# MCU.net
KiCad netlist of a schematic drawn in Altium Designer
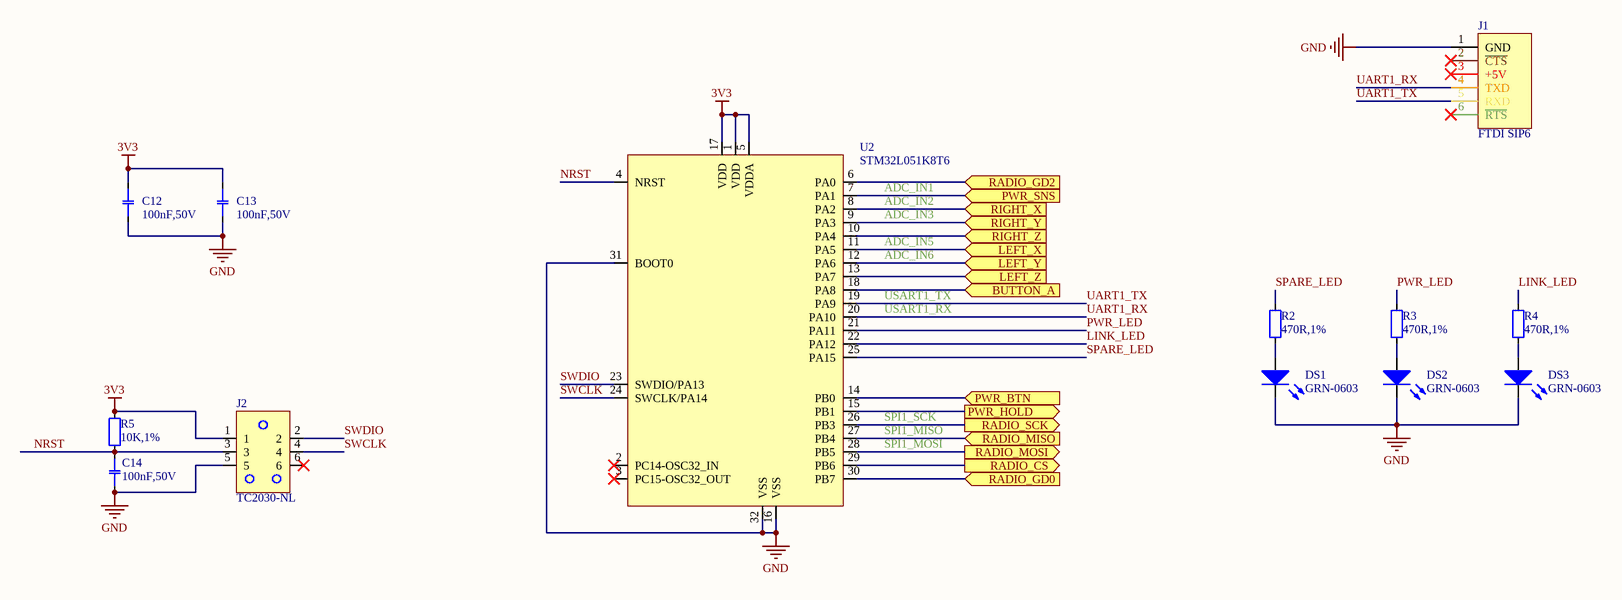
[diagram p0: MCU.SchDoc]

(export (version "E")
  (design (tool "Eeschema 10.0.6"))
  (components
    (comp (ref "C12")
      (value "100nF,50V")
      (footprint "CAPC1608X09N_0603")
      (description "CAP CER 0.1UF 50V 10% X7R 0603")
      (fields (field (name "MANUFACTURER") "Kemet") (field (name "TOLERANCE") "10%"))
      (libsource (lib "library") (part "CAP-NP_1"))
    )
    (comp (ref "C13")
      (value "100nF,50V")
      (footprint "CAPC1608X09N_0603")
      (description "CAP CER 0.1UF 50V 10% X7R 0603")
      (fields (field (name "MANUFACTURER") "Kemet") (field (name "TOLERANCE") "10%"))
      (libsource (lib "library") (part "CAP-NP_1"))
    )
    (comp (ref "C14")
      (value "100nF,50V")
      (footprint "CAPC1608X09N_0603")
      (description "CAP CER 0.1UF 50V 10% X7R 0603")
      (fields (field (name "MANUFACTURER") "Kemet") (field (name "TOLERANCE") "10%"))
      (libsource (lib "library") (part "CAP-NP_1"))
    )
    (comp (ref "DS1")
      (value "GRN-0603")
      (footprint "LED_SML-LX0603")
      (description "LED GREEN CLEAR 0603 SMD")
      (fields
        (field (name "MANUFACTURER") "Dialight")
        (field (name "MANUFACTURER PART NUMBER") "5988081107F")
      )
      (libsource (lib "library") (part "LED_1"))
    )
    (comp (ref "DS2")
      (value "GRN-0603")
      (footprint "LED_SML-LX0603")
      (description "LED GREEN CLEAR 0603 SMD")
      (fields
        (field (name "MANUFACTURER") "Dialight")
        (field (name "MANUFACTURER PART NUMBER") "5988081107F")
      )
      (libsource (lib "library") (part "LED_1"))
    )
    (comp (ref "DS3")
      (value "GRN-0603")
      (footprint "LED_SML-LX0603")
      (description "LED GREEN CLEAR 0603 SMD")
      (fields
        (field (name "MANUFACTURER") "Dialight")
        (field (name "MANUFACTURER PART NUMBER") "5988081107F")
      )
      (libsource (lib "library") (part "LED_1"))
    )
    (comp (ref "J1")
      (value "FTDI SIP6")
      (footprint "HIROSE_A2-6PA-2.54DSA")
      (description "FTDI Serial Header")
      (fields
        (field (name "MANUFACTURER") "Hirose Electric Co Ltd")
        (field (name "MANUFACTURER PART NUMBER") "A2-6PA-2.54DSA(71)")
      )
      (libsource (lib "library") (part "FTDI_TTL_232R"))
    )
    (comp (ref "J2")
      (value "TC2030-NL")
      (footprint "TAGCON_TC2030-IDC-NL")
      (description "Tag connect 6 way - No Legs")
      (libsource (lib "library") (part "TAGCON_TC2030-IDC"))
    )
    (comp (ref "R2")
      (value "470R,1%")
      (footprint "RESC1608X06N_0603")
      (description "RES 470 OHM 1/10W 1% 0603 SMD")
      (fields (field (name "MANUFACTURER") "Rohm Semiconductor") (field (name "POWER") "0.1W"))
      (libsource (lib "library") (part "RESISTOR_1"))
    )
    (comp (ref "R3")
      (value "470R,1%")
      (footprint "RESC1608X06N_0603")
      (description "RES 470 OHM 1/10W 1% 0603 SMD")
      (fields (field (name "MANUFACTURER") "Rohm Semiconductor") (field (name "POWER") "0.1W"))
      (libsource (lib "library") (part "RESISTOR_1"))
    )
    (comp (ref "R4")
      (value "470R,1%")
      (footprint "RESC1608X06N_0603")
      (description "RES 470 OHM 1/10W 1% 0603 SMD")
      (fields (field (name "MANUFACTURER") "Rohm Semiconductor") (field (name "POWER") "0.1W"))
      (libsource (lib "library") (part "RESISTOR_1"))
    )
    (comp (ref "R5")
      (value "10K,1%")
      (footprint "RESC1608X06N_0603")
      (description "RES 10.0K OHM 1/10W 1% 0603 SMD")
      (fields (field (name "MANUFACTURER") "Yageo") (field (name "POWER") "0.1W"))
      (libsource (lib "library") (part "RESISTOR_1"))
    )
    (comp (ref "U2")
      (value "STM32L051K8T6")
      (footprint "LQFP32")
      (description "32 Bit Mcirocontroler")
      (fields (field (name "MANUFACTURER") "ST Microelectronics"))
      (libsource (lib "library") (part "STM32L051x6/8"))
    )
  )
  (nets
    (net (code "1") (name "/BUTTON_A") (class "Default")
      (node (ref "U2") (pin "18") (pinfunction "PA8_18") (pintype "passive"))
    )
    (net (code "2") (name "/LEFT_X") (class "Default")
      (node (ref "U2") (pin "11") (pinfunction "PA5_11") (pintype "passive"))
    )
    (net (code "3") (name "/LEFT_Y") (class "Default")
      (node (ref "U2") (pin "12") (pinfunction "PA6_12") (pintype "passive"))
    )
    (net (code "4") (name "/LEFT_Z") (class "Default")
      (node (ref "U2") (pin "13") (pinfunction "PA7_13") (pintype "passive"))
    )
    (net (code "5") (name "/LINK_LED") (class "Default")
      (node (ref "R4") (pin "2") (pinfunction "2_2") (pintype "passive"))
      (node (ref "U2") (pin "22") (pinfunction "PA12_22") (pintype "passive"))
    )
    (net (code "6") (name "/NRST") (class "Default")
      (node (ref "C14") (pin "1") (pinfunction "1_1") (pintype "passive"))
      (node (ref "J2") (pin "3") (pinfunction "3_3") (pintype "passive"))
      (node (ref "R5") (pin "1") (pinfunction "1_1") (pintype "passive"))
      (node (ref "U2") (pin "4") (pinfunction "NRST_4") (pintype "passive"))
    )
    (net (code "7") (name "/PWR_BTN") (class "Default")
      (node (ref "U2") (pin "14") (pinfunction "PB0_14") (pintype "passive"))
    )
    (net (code "8") (name "/PWR_HOLD") (class "Default")
      (node (ref "U2") (pin "15") (pinfunction "PB1_15") (pintype "passive"))
    )
    (net (code "9") (name "/PWR_LED") (class "Default")
      (node (ref "R3") (pin "2") (pinfunction "2_2") (pintype "passive"))
      (node (ref "U2") (pin "21") (pinfunction "PA11_21") (pintype "passive"))
    )
    (net (code "10") (name "/PWR_SNS") (class "Default")
      (node (ref "U2") (pin "7") (pinfunction "PA1_7") (pintype "passive"))
    )
    (net (code "11") (name "/RADIO_CS") (class "Default")
      (node (ref "U2") (pin "29") (pinfunction "PB6_29") (pintype "passive"))
    )
    (net (code "12") (name "/RADIO_GD0") (class "Default")
      (node (ref "U2") (pin "30") (pinfunction "PB7_30") (pintype "passive"))
    )
    (net (code "13") (name "/RADIO_GD2") (class "Default")
      (node (ref "U2") (pin "6") (pinfunction "PA0_6") (pintype "passive"))
    )
    (net (code "14") (name "/RADIO_MISO") (class "Default")
      (node (ref "U2") (pin "27") (pinfunction "PB4_27") (pintype "passive"))
    )
    (net (code "15") (name "/RADIO_MOSI") (class "Default")
      (node (ref "U2") (pin "28") (pinfunction "PB5_28") (pintype "passive"))
    )
    (net (code "16") (name "/RADIO_SCK") (class "Default")
      (node (ref "U2") (pin "26") (pinfunction "PB3_26") (pintype "passive"))
    )
    (net (code "17") (name "/RIGHT_X") (class "Default")
      (node (ref "U2") (pin "8") (pinfunction "PA2_8") (pintype "passive"))
    )
    (net (code "18") (name "/RIGHT_Y") (class "Default")
      (node (ref "U2") (pin "9") (pinfunction "PA3_9") (pintype "passive"))
    )
    (net (code "19") (name "/RIGHT_Z") (class "Default")
      (node (ref "U2") (pin "10") (pinfunction "PA4_10") (pintype "passive"))
    )
    (net (code "20") (name "/SPARE_LED") (class "Default")
      (node (ref "R2") (pin "2") (pinfunction "2_2") (pintype "passive"))
      (node (ref "U2") (pin "25") (pinfunction "PA15_25") (pintype "passive"))
    )
    (net (code "21") (name "/SWCLK") (class "Default")
      (node (ref "J2") (pin "4") (pinfunction "4_4") (pintype "passive"))
      (node (ref "U2") (pin "24") (pinfunction "SWCLK/PA14_24") (pintype "passive"))
    )
    (net (code "22") (name "/SWDIO") (class "Default")
      (node (ref "J2") (pin "2") (pinfunction "2_2") (pintype "passive"))
      (node (ref "U2") (pin "23") (pinfunction "SWDIO/PA13_23") (pintype "passive"))
    )
    (net (code "23") (name "/UART1_RX") (class "Default")
      (node (ref "J1") (pin "4") (pinfunction "TXD_4") (pintype "passive"))
      (node (ref "U2") (pin "20") (pinfunction "PA10_20") (pintype "passive"))
    )
    (net (code "24") (name "/UART1_TX") (class "Default")
      (node (ref "J1") (pin "5") (pinfunction "RXD_5") (pintype "passive"))
      (node (ref "U2") (pin "19") (pinfunction "PA9_19") (pintype "passive"))
    )
    (net (code "25") (name "3V3") (class "Default")
      (node (ref "C12") (pin "2") (pinfunction "2_2") (pintype "passive"))
      (node (ref "C13") (pin "2") (pinfunction "2_2") (pintype "passive"))
      (node (ref "J2") (pin "1") (pinfunction "1_1") (pintype "passive"))
      (node (ref "R5") (pin "2") (pinfunction "2_2") (pintype "passive"))
      (node (ref "U2") (pin "1") (pinfunction "VDD_1") (pintype "passive"))
      (node (ref "U2") (pin "17") (pinfunction "VDD_17") (pintype "passive"))
      (node (ref "U2") (pin "5") (pinfunction "VDDA_5") (pintype "passive"))
    )
    (net (code "26") (name "GND") (class "Default")
      (node (ref "C12") (pin "1") (pinfunction "1_1") (pintype "passive"))
      (node (ref "C13") (pin "1") (pinfunction "1_1") (pintype "passive"))
      (node (ref "C14") (pin "2") (pinfunction "2_2") (pintype "passive"))
      (node (ref "DS1") (pin "1") (pinfunction "C_1") (pintype "passive"))
      (node (ref "DS2") (pin "1") (pinfunction "C_1") (pintype "passive"))
      (node (ref "DS3") (pin "1") (pinfunction "C_1") (pintype "passive"))
      (node (ref "J1") (pin "1") (pinfunction "GND_1") (pintype "passive"))
      (node (ref "J2") (pin "5") (pinfunction "5_5") (pintype "passive"))
      (node (ref "U2") (pin "16") (pinfunction "VSS_16") (pintype "passive"))
      (node (ref "U2") (pin "31") (pinfunction "BOOT0_31") (pintype "passive"))
      (node (ref "U2") (pin "32") (pinfunction "VSS_32") (pintype "passive"))
    )
    (net (code "27") (name "Net-(DS1-A)") (class "Default")
      (node (ref "DS1") (pin "2") (pinfunction "A_2") (pintype "passive"))
      (node (ref "R2") (pin "1") (pinfunction "1_1") (pintype "passive"))
    )
    (net (code "28") (name "Net-(DS2-A)") (class "Default")
      (node (ref "DS2") (pin "2") (pinfunction "A_2") (pintype "passive"))
      (node (ref "R3") (pin "1") (pinfunction "1_1") (pintype "passive"))
    )
    (net (code "29") (name "Net-(DS3-A)") (class "Default")
      (node (ref "DS3") (pin "2") (pinfunction "A_2") (pintype "passive"))
      (node (ref "R4") (pin "1") (pinfunction "1_1") (pintype "passive"))
    )
    (net (code "30") (name "unconnected-(J1-+5V-Pad3)") (class "Default")
      (node (ref "J1") (pin "3") (pinfunction "+5V_3") (pintype "passive+no_connect"))
    )
    (net (code "31") (name "unconnected-(J1-~{CTS}-Pad2)") (class "Default")
      (node (ref "J1") (pin "2") (pinfunction "~{CTS}_2") (pintype "passive+no_connect"))
    )
    (net (code "32") (name "unconnected-(J1-~{RTS}-Pad6)") (class "Default")
      (node (ref "J1") (pin "6") (pinfunction "~{RTS}_6") (pintype "passive+no_connect"))
    )
    (net (code "33") (name "unconnected-(J2-Pad6)") (class "Default")
      (node (ref "J2") (pin "6") (pinfunction "6_6") (pintype "passive+no_connect"))
    )
    (net (code "34") (name "unconnected-(U2-PC14-OSC32_IN-Pad2)") (class "Default")
      (node (ref "U2") (pin "2") (pinfunction "PC14-OSC32_IN_2") (pintype "passive+no_connect"))
    )
    (net (code "35") (name "unconnected-(U2-PC15-OSC32_OUT-Pad3)") (class "Default")
      (node (ref "U2") (pin "3") (pinfunction "PC15-OSC32_OUT_3") (pintype "passive+no_connect"))
    )
  )
)
